# PSU24V_for_FAN.net
KiCad netlist of a schematic drawn in Altium Designer
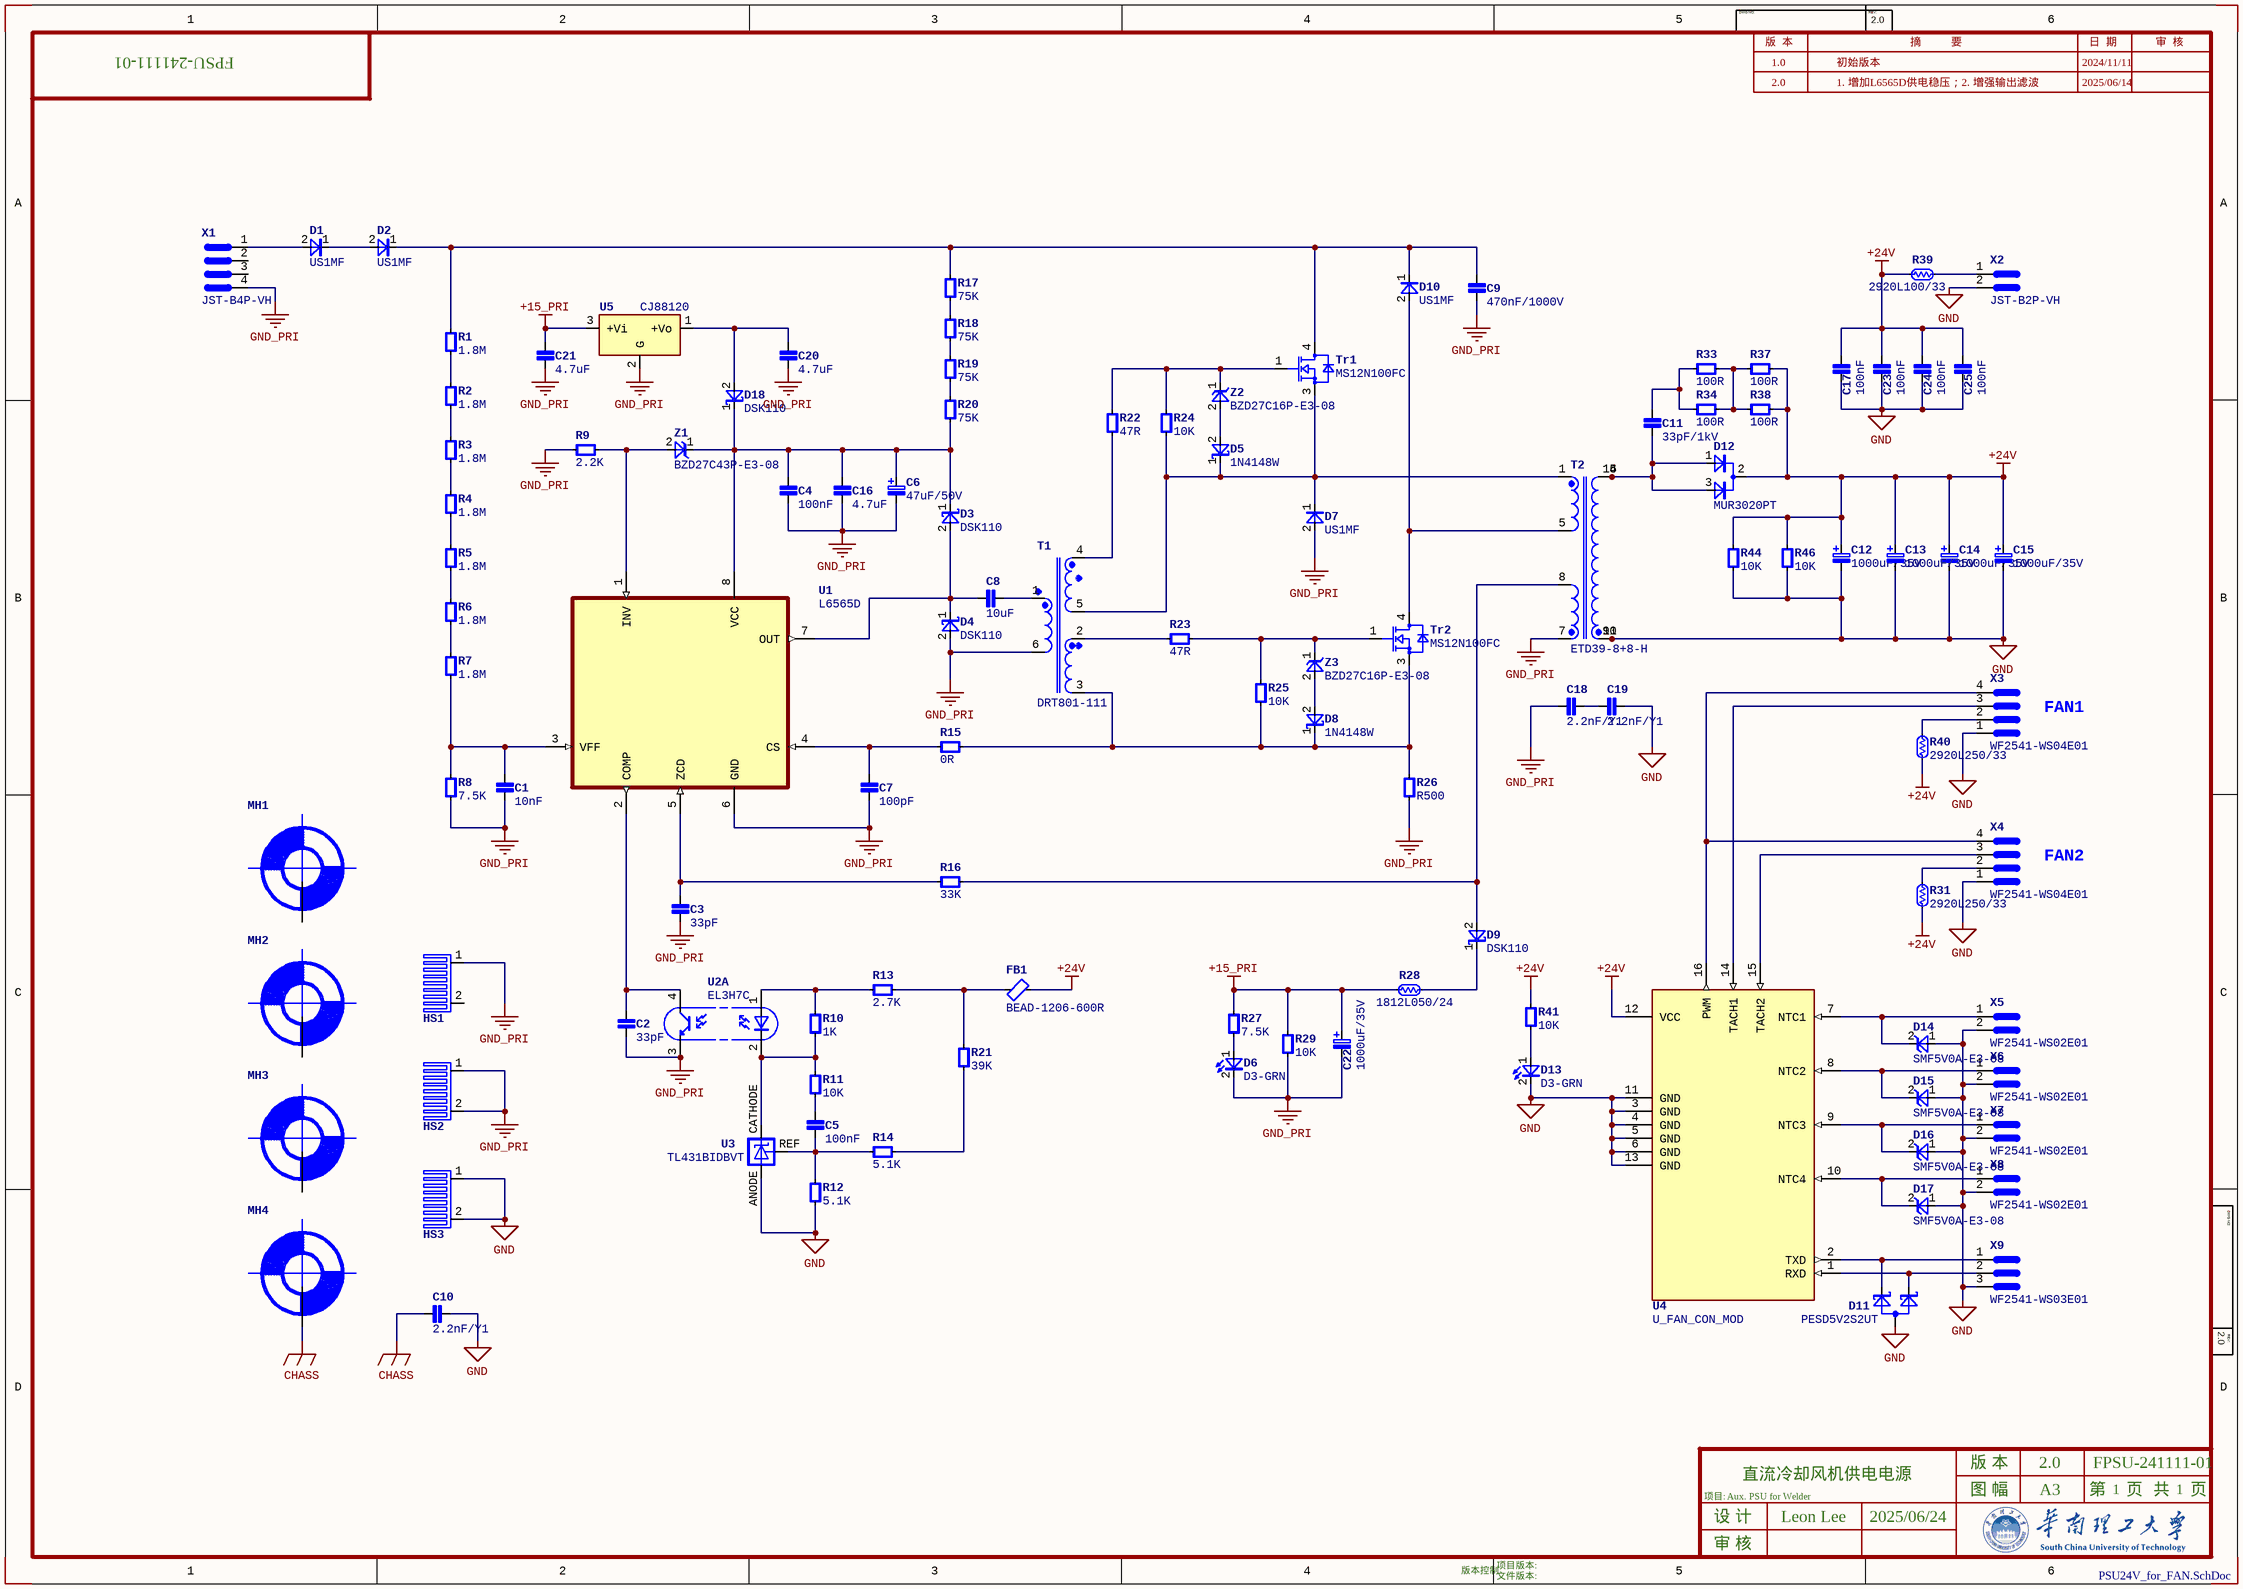
[diagram p0: PSU24V_for_FAN.SchDoc]

(export (version "E")
  (design (tool "Eeschema 10.0.6"))
  (components
    (comp (ref "C1")
      (value "10nF")
      (footprint "CAPC1206N")
      (libsource (lib "User_leo") (part "CAPACITOR(S)"))
    )
    (comp (ref "C2")
      (value "33pF")
      (footprint "CAPC1206N")
      (libsource (lib "User_leo") (part "CAPACITOR(S)"))
    )
    (comp (ref "C3")
      (value "33pF")
      (footprint "CAPC1206N")
      (libsource (lib "User_leo") (part "CAPACITOR(S)"))
    )
    (comp (ref "C4")
      (value "100nF")
      (footprint "CAPC1206N")
      (libsource (lib "User_leo") (part "CAPACITOR(S)"))
    )
    (comp (ref "C5") (value "100nF") (footprint "CAPC1206N") (libsource (lib "*") (part "CAPACITOR(S)")))
    (comp (ref "C6")
      (value "47uF/50V")
      (footprint "RB2.5M/D6.3")
      (libsource (lib "User_leo") (part "CAPACITOR POL(S)"))
    )
    (comp (ref "C7")
      (value "100pF")
      (footprint "CAPC1206N")
      (libsource (lib "User_leo") (part "CAPACITOR(S)"))
    )
    (comp (ref "C8")
      (value "10uF")
      (footprint "CAPC1206N")
      (libsource (lib "User_leo") (part "CAPACITOR(S)"))
    )
    (comp (ref "C9")
      (value "470nF/1000V")
      (footprint "PCM27.5-W17")
      (libsource (lib "User_leo") (part "CAPACITOR(S)"))
    )
    (comp (ref "C10")
      (value "2.2nF/Y1")
      (footprint "CAPRD10-10x5")
      (libsource (lib "User_leo") (part "CAPACITOR(S)"))
    )
    (comp (ref "C11")
      (value "33pF/1kV")
      (footprint "CAPC1206N")
      (libsource (lib "User_leo") (part "CAPACITOR(S)"))
    )
    (comp (ref "C12")
      (value "1000uF/35V")
      (footprint "RB5M/D10")
      (libsource (lib "User_leo") (part "CAPACITOR POL(S)"))
    )
    (comp (ref "C13")
      (value "1000uF/35V")
      (footprint "RB5M/D10")
      (libsource (lib "User_leo") (part "CAPACITOR POL(S)"))
    )
    (comp (ref "C14")
      (value "1000uF/35V")
      (footprint "RB5M/D10")
      (libsource (lib "User_leo") (part "CAPACITOR POL(S)"))
    )
    (comp (ref "C15")
      (value "1000uF/35V")
      (footprint "RB5M/D10")
      (libsource (lib "User_leo") (part "CAPACITOR POL(S)"))
    )
    (comp (ref "C16")
      (value "4.7uF")
      (footprint "CAPC1206N")
      (libsource (lib "User_leo") (part "CAPACITOR(S)"))
    )
    (comp (ref "C17")
      (value "100nF")
      (footprint "CAPC1206N")
      (libsource (lib "User_leo") (part "CAPACITOR(S)"))
    )
    (comp (ref "C18")
      (value "2.2nF/Y1")
      (footprint "CAPRD10-10x5")
      (libsource (lib "User_leo") (part "CAPACITOR(S)"))
    )
    (comp (ref "C19")
      (value "2.2nF/Y1")
      (footprint "CAPRD10-10x5")
      (libsource (lib "User_leo") (part "CAPACITOR(S)"))
    )
    (comp (ref "C20")
      (value "4.7uF")
      (footprint "CAPC1206N")
      (libsource (lib "User_leo") (part "CAPACITOR(S)"))
    )
    (comp (ref "C21")
      (value "4.7uF")
      (footprint "CAPC1206N")
      (libsource (lib "User_leo") (part "CAPACITOR(S)"))
    )
    (comp (ref "C22")
      (value "1000uF/35V")
      (footprint "RB5M/D10")
      (libsource (lib "User_leo") (part "CAPACITOR POL(S)"))
    )
    (comp (ref "C23")
      (value "100nF")
      (footprint "CAPC1206N")
      (libsource (lib "User_leo") (part "CAPACITOR(S)"))
    )
    (comp (ref "C24")
      (value "100nF")
      (footprint "CAPC1206N")
      (libsource (lib "User_leo") (part "CAPACITOR(S)"))
    )
    (comp (ref "C25")
      (value "100nF")
      (footprint "CAPC1206N")
      (libsource (lib "User_leo") (part "CAPACITOR(S)"))
    )
    (comp (ref "D1")
      (value "US1MF")
      (footprint "SMAF")
      (description "二极管")
      (libsource (lib "User_leo") (part "DIODE(S)"))
    )
    (comp (ref "D2")
      (value "US1MF")
      (footprint "SMAF")
      (description "二极管")
      (libsource (lib "User_leo") (part "DIODE(S)"))
    )
    (comp (ref "D3")
      (value "DSK110")
      (footprint "SMF-N-1K2A")
      (description "肖特基二极管")
      (libsource (lib "User_leo") (part "DIODE SCHOTTKY(S)"))
    )
    (comp (ref "D4")
      (value "DSK110")
      (footprint "SMF-N-1K2A")
      (description "肖特基二极管")
      (libsource (lib "User_leo") (part "DIODE SCHOTTKY(S)"))
    )
    (comp (ref "D5")
      (value "1N4148W")
      (footprint "SOD-123 - 1K2A")
      (description "肖特基二极管")
      (libsource (lib "User_leo") (part "DIODE SCHOTTKY(S)"))
    )
    (comp (ref "D6")
      (value "D3-GRN")
      (footprint "LED-D3")
      (description "发光二极管")
      (libsource (lib "User_leo") (part "LED(S)"))
    )
    (comp (ref "D7")
      (value "US1MF")
      (footprint "SMAF")
      (description "二极管")
      (libsource (lib "User_leo") (part "DIODE(S)"))
    )
    (comp (ref "D8")
      (value "1N4148W")
      (footprint "SOD-123 - 1K2A")
      (description "肖特基二极管")
      (libsource (lib "User_leo") (part "DIODE SCHOTTKY(S)"))
    )
    (comp (ref "D9")
      (value "DSK110")
      (footprint "SMF-N-1K2A")
      (description "肖特基二极管")
      (libsource (lib "User_leo") (part "DIODE SCHOTTKY(S)"))
    )
    (comp (ref "D10")
      (value "US1MF")
      (footprint "SMAF")
      (description "二极管")
      (libsource (lib "User_leo") (part "DIODE(S)"))
    )
    (comp (ref "D11")
      (value "PESD5V2S2UT")
      (footprint "SMD USER:SOT-23_N")
      (description "Schottky barrier (double) diodes")
      (libsource (lib "User_leo") (part "DIODE BAS40-06"))
    )
    (comp (ref "D12")
      (value "MUR3020PT")
      (footprint "PSU24_for_FAN:TO-247-3_Vertical")
      (description "快恢复二极管")
      (libsource (lib "User_leo") (part "DIODE MUR1620CT"))
    )
    (comp (ref "D13")
      (value "D3-GRN")
      (footprint "LED-D3")
      (description "发光二极管")
      (libsource (lib "User_leo") (part "LED(S)"))
    )
    (comp (ref "D14")
      (value "SMF5V0A-E3-08")
      (footprint "SMF-N")
      (description "齐纳二极管")
      (libsource (lib "User_leo") (part "DIODE ZENER(S)"))
    )
    (comp (ref "D15")
      (value "SMF5V0A-E3-08")
      (footprint "SMF-N")
      (description "齐纳二极管")
      (libsource (lib "User_leo") (part "DIODE ZENER(S)"))
    )
    (comp (ref "D16")
      (value "SMF5V0A-E3-08")
      (footprint "SMF-N")
      (description "齐纳二极管")
      (libsource (lib "User_leo") (part "DIODE ZENER(S)"))
    )
    (comp (ref "D17")
      (value "SMF5V0A-E3-08")
      (footprint "SMF-N")
      (description "齐纳二极管")
      (libsource (lib "User_leo") (part "DIODE ZENER(S)"))
    )
    (comp (ref "D18")
      (value "DSK110")
      (footprint "SMF-N-1K2A")
      (description "肖特基二极管")
      (libsource (lib "User_leo") (part "DIODE SCHOTTKY(S)"))
    )
    (comp (ref "FB1")
      (value "BEAD-1206-600R")
      (footprint "RESC1206N")
      (description "磁珠电感")
      (libsource (lib "User_leo") (part "FerriteBead1"))
    )
    (comp (ref "HS1")
      (value "HS-TO247-42x25x40")
      (footprint "HEATSINK_TO220_Vertical_42x25x38")
      (description "散热器, 2脚")
      (libsource (lib "User_leo") (part "HEATSINK_2PINS"))
    )
    (comp (ref "HS2")
      (value "HS-TO247-42x25x40")
      (footprint "HEATSINK_TO220_Vertical_42x25x38")
      (description "散热器, 2脚")
      (libsource (lib "User_leo") (part "HEATSINK_2PINS"))
    )
    (comp (ref "HS3")
      (value "HS-TO247-42x25x40")
      (footprint "HEATSINK_TO220_Vertical_42x25x38")
      (description "散热器, 2脚")
      (libsource (lib "User_leo") (part "HEATSINK_2PINS"))
    )
    (comp (ref "MH1")
      (value "MH1")
      (footprint "MH-D32-4x4")
      (description "安装孔")
      (libsource (lib "User_leo") (part "MH1"))
    )
    (comp (ref "MH2")
      (value "MH1")
      (footprint "MH-D32-4x4")
      (description "安装孔")
      (libsource (lib "User_leo") (part "MH1"))
    )
    (comp (ref "MH3")
      (value "MH1")
      (footprint "MH-D32-4x4")
      (description "安装孔")
      (libsource (lib "User_leo") (part "MH1"))
    )
    (comp (ref "MH4")
      (value "MH1")
      (footprint "MH-D32-4x4-PE")
      (description "安装孔")
      (libsource (lib "User_leo") (part "MH1"))
    )
    (comp (ref "R1")
      (value "1.8M")
      (footprint "RESC1206N")
      (description "电阻")
      (libsource (lib "User_leo") (part "RESISTOR(S)"))
    )
    (comp (ref "R2")
      (value "1.8M")
      (footprint "RESC1206N")
      (description "电阻")
      (libsource (lib "User_leo") (part "RESISTOR(S)"))
    )
    (comp (ref "R3")
      (value "1.8M")
      (footprint "RESC1206N")
      (description "电阻")
      (libsource (lib "User_leo") (part "RESISTOR(S)"))
    )
    (comp (ref "R4")
      (value "1.8M")
      (footprint "RESC1206N")
      (description "电阻")
      (libsource (lib "User_leo") (part "RESISTOR(S)"))
    )
    (comp (ref "R5")
      (value "1.8M")
      (footprint "RESC1206N")
      (description "电阻")
      (libsource (lib "User_leo") (part "RESISTOR(S)"))
    )
    (comp (ref "R6")
      (value "1.8M")
      (footprint "RESC1206N")
      (description "电阻")
      (libsource (lib "User_leo") (part "RESISTOR(S)"))
    )
    (comp (ref "R7")
      (value "1.8M")
      (footprint "RESC1206N")
      (description "电阻")
      (libsource (lib "User_leo") (part "RESISTOR(S)"))
    )
    (comp (ref "R8")
      (value "7.5K")
      (footprint "RESC1206N")
      (description "电阻")
      (libsource (lib "User_leo") (part "RESISTOR(S)"))
    )
    (comp (ref "R9")
      (value "2.2K")
      (footprint "RESC1206N")
      (description "电阻")
      (libsource (lib "User_leo") (part "RESISTOR(S)"))
    )
    (comp (ref "R10") (value "1K") (footprint "RESC1206N") (libsource (lib "*") (part "RESISTOR(S)")))
    (comp (ref "R11") (value "10K") (footprint "RESC1206N") (libsource (lib "*") (part "RESISTOR(S)")))
    (comp (ref "R12") (value "5.1K") (footprint "RESC1206N") (libsource (lib "*") (part "RESISTOR(S)")))
    (comp (ref "R13") (value "2.7K") (footprint "RESC1206N") (libsource (lib "*") (part "RESISTOR(S)")))
    (comp (ref "R14") (value "5.1K") (footprint "RESC1206N") (libsource (lib "*") (part "RESISTOR(S)")))
    (comp (ref "R15")
      (value "0R")
      (footprint "RESC1206N")
      (description "电阻")
      (libsource (lib "User_leo") (part "RESISTOR(S)"))
    )
    (comp (ref "R16")
      (value "33K")
      (footprint "RESC1206N")
      (description "电阻")
      (libsource (lib "User_leo") (part "RESISTOR(S)"))
    )
    (comp (ref "R17")
      (value "75K")
      (footprint "RESC1206N")
      (description "电阻")
      (libsource (lib "User_leo") (part "RESISTOR(S)"))
    )
    (comp (ref "R18")
      (value "75K")
      (footprint "RESC1206N")
      (description "电阻")
      (libsource (lib "User_leo") (part "RESISTOR(S)"))
    )
    (comp (ref "R19")
      (value "75K")
      (footprint "RESC1206N")
      (description "电阻")
      (libsource (lib "User_leo") (part "RESISTOR(S)"))
    )
    (comp (ref "R20")
      (value "75K")
      (footprint "RESC1206N")
      (description "电阻")
      (libsource (lib "User_leo") (part "RESISTOR(S)"))
    )
    (comp (ref "R21") (value "39K") (footprint "RESC1206N") (libsource (lib "*") (part "RESISTOR(S)")))
    (comp (ref "R22")
      (value "47R")
      (footprint "RESC1206N")
      (description "电阻")
      (libsource (lib "User_leo") (part "RESISTOR(S)"))
    )
    (comp (ref "R23")
      (value "47R")
      (footprint "RESC1206N")
      (description "电阻")
      (libsource (lib "User_leo") (part "RESISTOR(S)"))
    )
    (comp (ref "R24")
      (value "10K")
      (footprint "RESC1206N")
      (description "电阻")
      (libsource (lib "User_leo") (part "RESISTOR(S)"))
    )
    (comp (ref "R25")
      (value "10K")
      (footprint "RESC1206N")
      (description "电阻")
      (libsource (lib "User_leo") (part "RESISTOR(S)"))
    )
    (comp (ref "R26")
      (value "R500")
      (footprint "RESC1225N")
      (description "电阻")
      (libsource (lib "User_leo") (part "RESISTOR(S)"))
    )
    (comp (ref "R27") (value "7.5K") (footprint "RESC1206N") (libsource (lib "*") (part "RESISTOR(S)")))
    (comp (ref "R28")
      (value "1812L050/24")
      (footprint "PTCC1812N")
      (description "None Liner Resistor")
      (libsource (lib "User_leo") (part "RESISTOR(S) NL"))
    )
    (comp (ref "R29") (value "10K") (footprint "RESC1206N") (libsource (lib "*") (part "RESISTOR(S)")))
    (comp (ref "R31")
      (value "2920L250/33")
      (footprint "PTC2920N")
      (description "None Liner Resistor")
      (libsource (lib "User_leo") (part "RESISTOR(S) NL"))
    )
    (comp (ref "R33")
      (value "100R")
      (footprint "RESC1206N")
      (description "电阻")
      (libsource (lib "User_leo") (part "RESISTOR(S)"))
    )
    (comp (ref "R34")
      (value "100R")
      (footprint "RESC1206N")
      (description "电阻")
      (libsource (lib "User_leo") (part "RESISTOR(S)"))
    )
    (comp (ref "R37")
      (value "100R")
      (footprint "RESC1206N")
      (description "电阻")
      (libsource (lib "User_leo") (part "RESISTOR(S)"))
    )
    (comp (ref "R38")
      (value "100R")
      (footprint "RESC1206N")
      (description "电阻")
      (libsource (lib "User_leo") (part "RESISTOR(S)"))
    )
    (comp (ref "R39")
      (value "2920L100/33")
      (footprint "PTC2920N")
      (description "None Liner Resistor")
      (libsource (lib "User_leo") (part "RESISTOR(S) NL"))
    )
    (comp (ref "R40")
      (value "2920L250/33")
      (footprint "PTC2920N")
      (description "None Liner Resistor")
      (libsource (lib "User_leo") (part "RESISTOR(S) NL"))
    )
    (comp (ref "R41") (value "10K") (footprint "RESC1206N") (libsource (lib "*") (part "RESISTOR(S)")))
    (comp (ref "R44")
      (value "10K")
      (footprint "RESC1206N")
      (description "电阻")
      (libsource (lib "User_leo") (part "RESISTOR(S)"))
    )
    (comp (ref "R46")
      (value "10K")
      (footprint "RESC1206N")
      (description "电阻")
      (libsource (lib "User_leo") (part "RESISTOR(S)"))
    )
    (comp (ref "T1")
      (value "DRT801-111")
      (footprint "TRANS-DRT801-1+1+1")
      (description "IGBT驱动变压器, DRT801/111, 12.5x16.6mm")
      (libsource (lib "User_leo") (part "Transformer DRT801-111"))
    )
    (comp (ref "T2")
      (value "ETD39-8+8-H")
      (footprint "ETD39-8+8pins")
      (description "反激变压器，初级2组，次级2组，通用焊接电源风扇供电，24V+24V")
      (libsource (lib "User_leo") (part "TRANSFORM-Flyback_PSU_for_FAN"))
    )
    (comp (ref "Tr1")
      (value "MS12N100FC")
      (footprint "PSU24_for_FAN:TO-247-3_Vertical")
      (description "MOSFET N-CH D-PAK/TO252")
      (fields (field (name "MANUFACTURER") "Fairchild") (field (name "PART NUMBER") "SUD40N08-16-E3"))
      (libsource (lib "User_leo") (part "MOSFET - N-CH"))
    )
    (comp (ref "Tr2")
      (value "MS12N100FC")
      (footprint "PSU24_for_FAN:TO-247-3_Vertical")
      (description "MOSFET N-CH D-PAK/TO252")
      (fields (field (name "MANUFACTURER") "Fairchild") (field (name "PART NUMBER") "SUD40N08-16-E3"))
      (libsource (lib "User_leo") (part "MOSFET - N-CH"))
    )
    (comp (ref "U1")
      (value "L6565D")
      (footprint "SOIC-8N")
      (description "ST, QUASI-RESONANT SMPS CONTROLLER")
      (libsource (lib "User_leo") (part "L6565D"))
    )
    (comp (ref "U2")
      (value "EL3H7C")
      (footprint "FP-EL3H7-G-MFG")
      (libsource (lib "User_leo") (part "Optical-Couple"))
    )
    (comp (ref "U3")
      (value "TL431BIDBVT")
      (footprint "SOT23-5_N")
      (description "可调基准电压集成")
      (libsource (lib "d_user1") (part "TL431CLP"))
    )
    (comp (ref "U4")
      (value "U_FAN_CON_MOD")
      (footprint "U_FAN_CON")
      (description "直流风扇转速控制模块")
      (libsource (lib "User_leo") (part "U_FAN_CON_MOD"))
    )
    (comp (ref "U5") (value "CJ88120") (footprint "FP-SOT89-MFG") (libsource (lib "User_leo") (part "78LXX")))
    (comp (ref "X1")
      (value "JST-B4P-VH")
      (footprint "B4P-VH")
      (description "线路板接插件")
      (libsource (lib "User_leo") (part "4PIN-PCB-Connector"))
    )
    (comp (ref "X2")
      (value "JST-B2P-VH")
      (footprint "B2P-VH")
      (description "线路板接插件")
      (libsource (lib "User_leo") (part "2PIN-PCB-Connector"))
    )
    (comp (ref "X3")
      (value "WF2541-WS04E01")
      (footprint "PSU24_for_FAN:WF2541-WSXX01-4PIN")
      (description "线路板接插件")
      (libsource (lib "User_leo") (part "4PIN-PCB-Connector"))
    )
    (comp (ref "X4")
      (value "WF2541-WS04E01")
      (footprint "PSU24_for_FAN:WF2541-WSXX01-4PIN")
      (description "线路板接插件")
      (libsource (lib "User_leo") (part "4PIN-PCB-Connector"))
    )
    (comp (ref "X5")
      (value "WF2541-WS02E01")
      (footprint "PSU24_for_FAN:WF2541-WSXX01-2PIN")
      (description "线路板接插件")
      (libsource (lib "User_leo") (part "2PIN-PCB-Connector"))
    )
    (comp (ref "X6")
      (value "WF2541-WS02E01")
      (footprint "PSU24_for_FAN:WF2541-WSXX01-2PIN")
      (description "线路板接插件")
      (libsource (lib "User_leo") (part "2PIN-PCB-Connector"))
    )
    (comp (ref "X7")
      (value "WF2541-WS02E01")
      (footprint "PSU24_for_FAN:WF2541-WSXX01-2PIN")
      (description "线路板接插件")
      (libsource (lib "User_leo") (part "2PIN-PCB-Connector"))
    )
    (comp (ref "X8")
      (value "WF2541-WS02E01")
      (footprint "PSU24_for_FAN:WF2541-WSXX01-2PIN")
      (description "线路板接插件")
      (libsource (lib "User_leo") (part "2PIN-PCB-Connector"))
    )
    (comp (ref "X9")
      (value "WF2541-WS03E01")
      (footprint "WF2541-WSXX01-3PIN")
      (description "线路板接插件")
      (libsource (lib "User_leo") (part "3PIN-PCB-Connector"))
    )
    (comp (ref "Z1")
      (value "BZD27C43P-E3-08")
      (footprint "SOD-123 - 1K2A")
      (description "齐纳二极管")
      (libsource (lib "") (part "DIODE ZENER(S)_1"))
    )
    (comp (ref "Z2")
      (value "BZD27C16P-E3-08")
      (footprint "SOD-123 - 1K2A")
      (description "齐纳二极管")
      (libsource (lib "") (part "DIODE ZENER(S)_1"))
    )
    (comp (ref "Z3")
      (value "BZD27C16P-E3-08")
      (footprint "SOD-123 - 1K2A")
      (description "齐纳二极管")
      (libsource (lib "") (part "DIODE ZENER(S)_1"))
    )
  )
  (nets
    (net (code "1") (name "+15_PRI") (class "Default")
      (node (ref "C21") (pin "1") (pinfunction "1_1") (pintype "passive"))
      (node (ref "C22") (pin "1") (pinfunction "1_1") (pintype "passive"))
      (node (ref "R27") (pin "2") (pinfunction "2_2") (pintype "passive"))
      (node (ref "R28") (pin "1") (pinfunction "1_1") (pintype "passive"))
      (node (ref "R29") (pin "2") (pinfunction "2_2") (pintype "passive"))
      (node (ref "U5") (pin "3") (pinfunction "+Vi_3") (pintype "passive"))
    )
    (net (code "2") (name "+24V") (class "Default")
      (node (ref "C12") (pin "1") (pinfunction "1_1") (pintype "passive"))
      (node (ref "C13") (pin "1") (pinfunction "1_1") (pintype "passive"))
      (node (ref "C14") (pin "1") (pinfunction "1_1") (pintype "passive"))
      (node (ref "C15") (pin "1") (pinfunction "1_1") (pintype "passive"))
      (node (ref "C17") (pin "1") (pinfunction "1_1") (pintype "passive"))
      (node (ref "C23") (pin "1") (pinfunction "1_1") (pintype "passive"))
      (node (ref "C24") (pin "1") (pinfunction "1_1") (pintype "passive"))
      (node (ref "C25") (pin "1") (pinfunction "1_1") (pintype "passive"))
      (node (ref "D12") (pin "2") (pinfunction "K_2") (pintype "passive"))
      (node (ref "FB1") (pin "2") (pinfunction "2_2") (pintype "passive"))
      (node (ref "R31") (pin "1") (pinfunction "1_1") (pintype "passive"))
      (node (ref "R37") (pin "1") (pinfunction "1_1") (pintype "passive"))
      (node (ref "R38") (pin "1") (pinfunction "1_1") (pintype "passive"))
      (node (ref "R39") (pin "1") (pinfunction "1_1") (pintype "passive"))
      (node (ref "R40") (pin "1") (pinfunction "1_1") (pintype "passive"))
      (node (ref "R41") (pin "2") (pinfunction "2_2") (pintype "passive"))
      (node (ref "R44") (pin "1") (pinfunction "1_1") (pintype "passive"))
      (node (ref "R46") (pin "1") (pinfunction "1_1") (pintype "passive"))
      (node (ref "U4") (pin "12") (pinfunction "VCC_12") (pintype "power_in"))
    )
    (net (code "3") (name "CHASS") (class "Default")
      (node (ref "C10") (pin "2") (pinfunction "2_2") (pintype "passive"))
      (node (ref "MH4") (pin "0") (pinfunction "0_0") (pintype "passive"))
    )
    (net (code "4") (name "GND") (class "Default")
      (node (ref "C10") (pin "1") (pinfunction "1_1") (pintype "passive"))
      (node (ref "C12") (pin "2") (pinfunction "2_2") (pintype "passive"))
      (node (ref "C13") (pin "2") (pinfunction "2_2") (pintype "passive"))
      (node (ref "C14") (pin "2") (pinfunction "2_2") (pintype "passive"))
      (node (ref "C15") (pin "2") (pinfunction "2_2") (pintype "passive"))
      (node (ref "C17") (pin "2") (pinfunction "2_2") (pintype "passive"))
      (node (ref "C19") (pin "1") (pinfunction "1_1") (pintype "passive"))
      (node (ref "C23") (pin "2") (pinfunction "2_2") (pintype "passive"))
      (node (ref "C24") (pin "2") (pinfunction "2_2") (pintype "passive"))
      (node (ref "C25") (pin "2") (pinfunction "2_2") (pintype "passive"))
      (node (ref "D11") (pin "3") (pinfunction "A_3") (pintype "passive"))
      (node (ref "D13") (pin "2") (pinfunction "K_2") (pintype "passive"))
      (node (ref "D14") (pin "1") (pinfunction "A_1") (pintype "passive"))
      (node (ref "D15") (pin "1") (pinfunction "A_1") (pintype "passive"))
      (node (ref "D16") (pin "1") (pinfunction "A_1") (pintype "passive"))
      (node (ref "D17") (pin "1") (pinfunction "A_1") (pintype "passive"))
      (node (ref "HS3") (pin "1") (pinfunction "1_1") (pintype "passive"))
      (node (ref "HS3") (pin "2") (pinfunction "2_2") (pintype "passive"))
      (node (ref "R12") (pin "1") (pinfunction "1_1") (pintype "passive"))
      (node (ref "R44") (pin "2") (pinfunction "2_2") (pintype "passive"))
      (node (ref "R46") (pin "2") (pinfunction "2_2") (pintype "passive"))
      (node (ref "T2") (pin "10") (pintype "passive"))
      (node (ref "T2") (pin "11") (pintype "passive"))
      (node (ref "T2") (pin "9") (pintype "passive"))
      (node (ref "U3") (pin "ANODE") (pinfunction "ANODE_ANODE") (pintype "passive"))
      (node (ref "U4") (pin "11") (pinfunction "GND_11") (pintype "power_in"))
      (node (ref "U4") (pin "13") (pinfunction "GND_13") (pintype "power_in"))
      (node (ref "U4") (pin "3") (pinfunction "GND_3") (pintype "power_in"))
      (node (ref "U4") (pin "4") (pinfunction "GND_4") (pintype "power_in"))
      (node (ref "U4") (pin "5") (pinfunction "GND_5") (pintype "power_in"))
      (node (ref "U4") (pin "6") (pinfunction "GND_6") (pintype "power_in"))
      (node (ref "X2") (pin "2") (pinfunction "2_2") (pintype "passive"))
      (node (ref "X3") (pin "1") (pinfunction "1_1") (pintype "passive"))
      (node (ref "X4") (pin "1") (pinfunction "1_1") (pintype "passive"))
      (node (ref "X5") (pin "2") (pinfunction "2_2") (pintype "passive"))
      (node (ref "X6") (pin "2") (pinfunction "2_2") (pintype "passive"))
      (node (ref "X7") (pin "2") (pinfunction "2_2") (pintype "passive"))
      (node (ref "X8") (pin "2") (pinfunction "2_2") (pintype "passive"))
      (node (ref "X9") (pin "3") (pinfunction "3_3") (pintype "passive"))
    )
    (net (code "5") (name "GND_PRI") (class "Default")
      (node (ref "C1") (pin "2") (pinfunction "2_2") (pintype "passive"))
      (node (ref "C16") (pin "2") (pinfunction "2_2") (pintype "passive"))
      (node (ref "C18") (pin "2") (pinfunction "2_2") (pintype "passive"))
      (node (ref "C2") (pin "2") (pinfunction "2_2") (pintype "passive"))
      (node (ref "C20") (pin "2") (pinfunction "2_2") (pintype "passive"))
      (node (ref "C21") (pin "2") (pinfunction "2_2") (pintype "passive"))
      (node (ref "C22") (pin "2") (pinfunction "2_2") (pintype "passive"))
      (node (ref "C3") (pin "2") (pinfunction "2_2") (pintype "passive"))
      (node (ref "C4") (pin "2") (pinfunction "2_2") (pintype "passive"))
      (node (ref "C6") (pin "2") (pinfunction "2_2") (pintype "passive"))
      (node (ref "C7") (pin "2") (pinfunction "2_2") (pintype "passive"))
      (node (ref "C9") (pin "2") (pinfunction "2_2") (pintype "passive"))
      (node (ref "D4") (pin "2") (pinfunction "A_2") (pintype "passive"))
      (node (ref "D6") (pin "2") (pinfunction "K_2") (pintype "passive"))
      (node (ref "D7") (pin "2") (pinfunction "A_2") (pintype "passive"))
      (node (ref "HS1") (pin "1") (pinfunction "1_1") (pintype "passive"))
      (node (ref "HS2") (pin "1") (pinfunction "1_1") (pintype "passive"))
      (node (ref "HS2") (pin "2") (pinfunction "2_2") (pintype "passive"))
      (node (ref "R26") (pin "2") (pinfunction "2_2") (pintype "passive"))
      (node (ref "R29") (pin "1") (pinfunction "1_1") (pintype "passive"))
      (node (ref "R8") (pin "2") (pinfunction "2_2") (pintype "passive"))
      (node (ref "R9") (pin "2") (pinfunction "2_2") (pintype "passive"))
      (node (ref "T1") (pin "6") (pinfunction "6_6") (pintype "passive"))
      (node (ref "T2") (pin "7") (pintype "passive"))
      (node (ref "U1") (pin "6") (pinfunction "GND_6") (pintype "power_in"))
      (node (ref "U2") (pin "3") (pinfunction "E_3") (pintype "passive"))
      (node (ref "U5") (pin "2") (pinfunction "G_2") (pintype "passive"))
      (node (ref "X1") (pin "4") (pinfunction "4_4") (pintype "passive"))
    )
    (net (code "6") (name "Net-(C5-Pad1)") (class "Default")
      (node (ref "C5") (pin "1") (pinfunction "1_1") (pintype "passive"))
      (node (ref "R11") (pin "1") (pinfunction "1_1") (pintype "passive"))
    )
    (net (code "7") (name "Net-(C5-Pad2)") (class "Default")
      (node (ref "C5") (pin "2") (pinfunction "2_2") (pintype "passive"))
      (node (ref "R12") (pin "2") (pinfunction "2_2") (pintype "passive"))
      (node (ref "R14") (pin "1") (pinfunction "1_1") (pintype "passive"))
      (node (ref "U3") (pin "REF") (pinfunction "REF_REF") (pintype "passive"))
    )
    (net (code "8") (name "Net-(C8-Pad2)") (class "Default")
      (node (ref "C8") (pin "2") (pinfunction "2_2") (pintype "passive"))
      (node (ref "T1") (pin "1") (pinfunction "1_1") (pintype "passive"))
    )
    (net (code "9") (name "Net-(C11-Pad1)") (class "Default")
      (node (ref "C11") (pin "1") (pinfunction "1_1") (pintype "passive"))
      (node (ref "R33") (pin "2") (pinfunction "2_2") (pintype "passive"))
      (node (ref "R34") (pin "2") (pinfunction "2_2") (pintype "passive"))
    )
    (net (code "10") (name "Net-(C11-Pad2)") (class "Default")
      (node (ref "C11") (pin "2") (pinfunction "2_2") (pintype "passive"))
      (node (ref "D12") (pin "1") (pinfunction "A_1") (pintype "passive"))
      (node (ref "D12") (pin "3") (pinfunction "A_3") (pintype "passive"))
      (node (ref "T2") (pin "14") (pintype "passive"))
      (node (ref "T2") (pin "15") (pintype "passive"))
      (node (ref "T2") (pin "16") (pintype "passive"))
    )
    (net (code "11") (name "Net-(C18-Pad1)") (class "Default")
      (node (ref "C18") (pin "1") (pinfunction "1_1") (pintype "passive"))
      (node (ref "C19") (pin "2") (pinfunction "2_2") (pintype "passive"))
    )
    (net (code "12") (name "Net-(D1-A)") (class "Default")
      (node (ref "D1") (pin "2") (pinfunction "A_2") (pintype "passive"))
      (node (ref "X1") (pin "1") (pinfunction "1_1") (pintype "passive"))
    )
    (net (code "13") (name "Net-(D1-K)") (class "Default")
      (node (ref "D1") (pin "1") (pinfunction "K_1") (pintype "passive"))
      (node (ref "D2") (pin "2") (pinfunction "A_2") (pintype "passive"))
    )
    (net (code "14") (name "Net-(D3-A)") (class "Default")
      (node (ref "C8") (pin "1") (pinfunction "1_1") (pintype "passive"))
      (node (ref "D3") (pin "2") (pinfunction "A_2") (pintype "passive"))
      (node (ref "D4") (pin "1") (pinfunction "K_1") (pintype "passive"))
      (node (ref "U1") (pin "7") (pinfunction "OUT_7") (pintype "output"))
    )
    (net (code "15") (name "Net-(D5-A)") (class "Default")
      (node (ref "D5") (pin "2") (pinfunction "A_2") (pintype "passive"))
      (node (ref "Z2") (pin "2") (pinfunction "A_2") (pintype "passive"))
    )
    (net (code "16") (name "Net-(D5-K)") (class "Default")
      (node (ref "D5") (pin "1") (pinfunction "K_1") (pintype "passive"))
      (node (ref "D7") (pin "1") (pinfunction "K_1") (pintype "passive"))
      (node (ref "R24") (pin "1") (pinfunction "1_1") (pintype "passive"))
      (node (ref "T1") (pin "5") (pinfunction "5_5") (pintype "passive"))
      (node (ref "T2") (pin "1") (pintype "passive"))
      (node (ref "Tr1") (pin "3") (pinfunction "S_3") (pintype "passive"))
    )
    (net (code "17") (name "Net-(D6-A)") (class "Default")
      (node (ref "D6") (pin "1") (pinfunction "A_1") (pintype "passive"))
      (node (ref "R27") (pin "1") (pinfunction "1_1") (pintype "passive"))
    )
    (net (code "18") (name "Net-(D8-A)") (class "Default")
      (node (ref "D8") (pin "2") (pinfunction "A_2") (pintype "passive"))
      (node (ref "Z3") (pin "2") (pinfunction "A_2") (pintype "passive"))
    )
    (net (code "19") (name "Net-(D8-K)") (class "Default")
      (node (ref "D8") (pin "1") (pinfunction "K_1") (pintype "passive"))
      (node (ref "R15") (pin "2") (pinfunction "2_2") (pintype "passive"))
      (node (ref "R25") (pin "1") (pinfunction "1_1") (pintype "passive"))
      (node (ref "R26") (pin "1") (pinfunction "1_1") (pintype "passive"))
      (node (ref "T1") (pin "3") (pinfunction "3_3") (pintype "passive"))
      (node (ref "Tr2") (pin "3") (pinfunction "S_3") (pintype "passive"))
    )
    (net (code "20") (name "Net-(D9-A)") (class "Default")
      (node (ref "D9") (pin "2") (pinfunction "A_2") (pintype "passive"))
      (node (ref "R16") (pin "2") (pinfunction "2_2") (pintype "passive"))
      (node (ref "T2") (pin "8") (pintype "passive"))
    )
    (net (code "21") (name "Net-(D9-K)") (class "Default")
      (node (ref "D9") (pin "1") (pinfunction "K_1") (pintype "passive"))
      (node (ref "R28") (pin "2") (pinfunction "2_2") (pintype "passive"))
    )
    (net (code "22") (name "Net-(D10-A)") (class "Default")
      (node (ref "D10") (pin "2") (pinfunction "A_2") (pintype "passive"))
      (node (ref "T2") (pin "5") (pintype "passive"))
      (node (ref "Tr2") (pin "4") (pinfunction "D_4") (pintype "passive"))
    )
    (net (code "23") (name "Net-(D10-K)") (class "Default")
      (node (ref "C9") (pin "1") (pinfunction "1_1") (pintype "passive"))
      (node (ref "D10") (pin "1") (pinfunction "K_1") (pintype "passive"))
      (node (ref "D2") (pin "1") (pinfunction "K_1") (pintype "passive"))
      (node (ref "R1") (pin "1") (pinfunction "1_1") (pintype "passive"))
      (node (ref "R17") (pin "2") (pinfunction "2_2") (pintype "passive"))
      (node (ref "Tr1") (pin "4") (pinfunction "D_4") (pintype "passive"))
    )
    (net (code "24") (name "Net-(D11-K1)") (class "Default")
      (node (ref "D11") (pin "1") (pinfunction "K1_1") (pintype "passive"))
      (node (ref "U4") (pin "2") (pinfunction "TXD_2") (pintype "output"))
      (node (ref "X9") (pin "1") (pinfunction "1_1") (pintype "passive"))
    )
    (net (code "25") (name "Net-(D11-K2)") (class "Default")
      (node (ref "D11") (pin "2") (pinfunction "K2_2") (pintype "passive"))
      (node (ref "U4") (pin "1") (pinfunction "RXD_1") (pintype "input"))
      (node (ref "X9") (pin "2") (pinfunction "2_2") (pintype "passive"))
    )
    (net (code "26") (name "Net-(D13-A)") (class "Default")
      (node (ref "D13") (pin "1") (pinfunction "A_1") (pintype "passive"))
      (node (ref "R41") (pin "1") (pinfunction "1_1") (pintype "passive"))
    )
    (net (code "27") (name "Net-(D14-K)") (class "Default")
      (node (ref "D14") (pin "2") (pinfunction "K_2") (pintype "passive"))
      (node (ref "U4") (pin "7") (pinfunction "NTC1_7") (pintype "input"))
      (node (ref "X5") (pin "1") (pinfunction "1_1") (pintype "passive"))
    )
    (net (code "28") (name "Net-(D15-K)") (class "Default")
      (node (ref "D15") (pin "2") (pinfunction "K_2") (pintype "passive"))
      (node (ref "U4") (pin "8") (pinfunction "NTC2_8") (pintype "input"))
      (node (ref "X6") (pin "1") (pinfunction "1_1") (pintype "passive"))
    )
    (net (code "29") (name "Net-(D16-K)") (class "Default")
      (node (ref "D16") (pin "2") (pinfunction "K_2") (pintype "passive"))
      (node (ref "U4") (pin "9") (pinfunction "NTC3_9") (pintype "input"))
      (node (ref "X7") (pin "1") (pinfunction "1_1") (pintype "passive"))
    )
    (net (code "30") (name "Net-(D17-K)") (class "Default")
      (node (ref "D17") (pin "2") (pinfunction "K_2") (pintype "passive"))
      (node (ref "U4") (pin "10") (pinfunction "NTC4_10") (pintype "input"))
      (node (ref "X8") (pin "1") (pinfunction "1_1") (pintype "passive"))
    )
    (net (code "31") (name "Net-(D18-A)") (class "Default")
      (node (ref "C20") (pin "1") (pinfunction "1_1") (pintype "passive"))
      (node (ref "D18") (pin "2") (pinfunction "A_2") (pintype "passive"))
      (node (ref "U5") (pin "1") (pinfunction "+Vo_1") (pintype "passive"))
    )
    (net (code "32") (name "Net-(D18-K)") (class "Default")
      (node (ref "C16") (pin "1") (pinfunction "1_1") (pintype "passive"))
      (node (ref "C4") (pin "1") (pinfunction "1_1") (pintype "passive"))
      (node (ref "C6") (pin "1") (pinfunction "1_1") (pintype "passive"))
      (node (ref "D18") (pin "1") (pinfunction "K_1") (pintype "passive"))
      (node (ref "D3") (pin "1") (pinfunction "K_1") (pintype "passive"))
      (node (ref "R20") (pin "1") (pinfunction "1_1") (pintype "passive"))
      (node (ref "U1") (pin "8") (pinfunction "VCC_8") (pintype "power_in"))
      (node (ref "Z1") (pin "1") (pinfunction "K_1") (pintype "passive"))
    )
    (net (code "33") (name "Net-(FB1-Pad1)") (class "Default")
      (node (ref "FB1") (pin "1") (pinfunction "1_1") (pintype "passive"))
      (node (ref "R13") (pin "2") (pinfunction "2_2") (pintype "passive"))
      (node (ref "R21") (pin "2") (pinfunction "2_2") (pintype "passive"))
    )
    (net (code "34") (name "Net-(R1-Pad2)") (class "Default")
      (node (ref "R1") (pin "2") (pinfunction "2_2") (pintype "passive"))
      (node (ref "R2") (pin "1") (pinfunction "1_1") (pintype "passive"))
    )
    (net (code "35") (name "Net-(R2-Pad2)") (class "Default")
      (node (ref "R2") (pin "2") (pinfunction "2_2") (pintype "passive"))
      (node (ref "R3") (pin "1") (pinfunction "1_1") (pintype "passive"))
    )
    (net (code "36") (name "Net-(R3-Pad2)") (class "Default")
      (node (ref "R3") (pin "2") (pinfunction "2_2") (pintype "passive"))
      (node (ref "R4") (pin "1") (pinfunction "1_1") (pintype "passive"))
    )
    (net (code "37") (name "Net-(R4-Pad2)") (class "Default")
      (node (ref "R4") (pin "2") (pinfunction "2_2") (pintype "passive"))
      (node (ref "R5") (pin "1") (pinfunction "1_1") (pintype "passive"))
    )
    (net (code "38") (name "Net-(R5-Pad2)") (class "Default")
      (node (ref "R5") (pin "2") (pinfunction "2_2") (pintype "passive"))
      (node (ref "R6") (pin "1") (pinfunction "1_1") (pintype "passive"))
    )
    (net (code "39") (name "Net-(R6-Pad2)") (class "Default")
      (node (ref "R6") (pin "2") (pinfunction "2_2") (pintype "passive"))
      (node (ref "R7") (pin "1") (pinfunction "1_1") (pintype "passive"))
    )
    (net (code "40") (name "Net-(R14-Pad2)") (class "Default")
      (node (ref "R14") (pin "2") (pinfunction "2_2") (pintype "passive"))
      (node (ref "R21") (pin "1") (pinfunction "1_1") (pintype "passive"))
    )
    (net (code "41") (name "Net-(R17-Pad1)") (class "Default")
      (node (ref "R17") (pin "1") (pinfunction "1_1") (pintype "passive"))
      (node (ref "R18") (pin "2") (pinfunction "2_2") (pintype "passive"))
    )
    (net (code "42") (name "Net-(R18-Pad1)") (class "Default")
      (node (ref "R18") (pin "1") (pinfunction "1_1") (pintype "passive"))
      (node (ref "R19") (pin "2") (pinfunction "2_2") (pintype "passive"))
    )
    (net (code "43") (name "Net-(R19-Pad1)") (class "Default")
      (node (ref "R19") (pin "1") (pinfunction "1_1") (pintype "passive"))
      (node (ref "R20") (pin "2") (pinfunction "2_2") (pintype "passive"))
    )
    (net (code "44") (name "Net-(R22-Pad1)") (class "Default")
      (node (ref "R22") (pin "1") (pinfunction "1_1") (pintype "passive"))
      (node (ref "T1") (pin "4") (pinfunction "4_4") (pintype "passive"))
    )
    (net (code "45") (name "Net-(R23-Pad2)") (class "Default")
      (node (ref "R23") (pin "2") (pinfunction "2_2") (pintype "passive"))
      (node (ref "T1") (pin "2") (pinfunction "2_2") (pintype "passive"))
    )
    (net (code "46") (name "Net-(R31-Pad2)") (class "Default")
      (node (ref "R31") (pin "2") (pinfunction "2_2") (pintype "passive"))
      (node (ref "X4") (pin "2") (pinfunction "2_2") (pintype "passive"))
    )
    (net (code "47") (name "Net-(R33-Pad1)") (class "Default")
      (node (ref "R33") (pin "1") (pinfunction "1_1") (pintype "passive"))
      (node (ref "R34") (pin "1") (pinfunction "1_1") (pintype "passive"))
      (node (ref "R37") (pin "2") (pinfunction "2_2") (pintype "passive"))
      (node (ref "R38") (pin "2") (pinfunction "2_2") (pintype "passive"))
    )
    (net (code "48") (name "Net-(R39-Pad2)") (class "Default")
      (node (ref "R39") (pin "2") (pinfunction "2_2") (pintype "passive"))
      (node (ref "X2") (pin "1") (pinfunction "1_1") (pintype "passive"))
    )
    (net (code "49") (name "Net-(R40-Pad2)") (class "Default")
      (node (ref "R40") (pin "2") (pinfunction "2_2") (pintype "passive"))
      (node (ref "X3") (pin "2") (pinfunction "2_2") (pintype "passive"))
    )
    (net (code "50") (name "Net-(Tr1-G)") (class "Default")
      (node (ref "R22") (pin "2") (pinfunction "2_2") (pintype "passive"))
      (node (ref "R24") (pin "2") (pinfunction "2_2") (pintype "passive"))
      (node (ref "Tr1") (pin "1") (pinfunction "G_1") (pintype "passive"))
      (node (ref "Z2") (pin "1") (pinfunction "K_1") (pintype "passive"))
    )
    (net (code "51") (name "Net-(Tr2-G)") (class "Default")
      (node (ref "R23") (pin "1") (pinfunction "1_1") (pintype "passive"))
      (node (ref "R25") (pin "2") (pinfunction "2_2") (pintype "passive"))
      (node (ref "Tr2") (pin "1") (pinfunction "G_1") (pintype "passive"))
      (node (ref "Z3") (pin "1") (pinfunction "K_1") (pintype "passive"))
    )
    (net (code "52") (name "Net-(U1-COMP)") (class "Default")
      (node (ref "C2") (pin "1") (pinfunction "1_1") (pintype "passive"))
      (node (ref "U1") (pin "2") (pinfunction "COMP_2") (pintype "output"))
      (node (ref "U2") (pin "4") (pinfunction "C_4") (pintype "passive"))
    )
    (net (code "53") (name "Net-(U1-CS)") (class "Default")
      (node (ref "C7") (pin "1") (pinfunction "1_1") (pintype "passive"))
      (node (ref "R15") (pin "1") (pinfunction "1_1") (pintype "passive"))
      (node (ref "U1") (pin "4") (pinfunction "CS_4") (pintype "input"))
    )
    (net (code "54") (name "Net-(U1-INV)") (class "Default")
      (node (ref "R9") (pin "1") (pinfunction "1_1") (pintype "passive"))
      (node (ref "U1") (pin "1") (pinfunction "INV_1") (pintype "input"))
      (node (ref "Z1") (pin "2") (pinfunction "A_2") (pintype "passive"))
    )
    (net (code "55") (name "Net-(U1-VFF)") (class "Default")
      (node (ref "C1") (pin "1") (pinfunction "1_1") (pintype "passive"))
      (node (ref "R7") (pin "2") (pinfunction "2_2") (pintype "passive"))
      (node (ref "R8") (pin "1") (pinfunction "1_1") (pintype "passive"))
      (node (ref "U1") (pin "3") (pinfunction "VFF_3") (pintype "input"))
    )
    (net (code "56") (name "Net-(U1-ZCD)") (class "Default")
      (node (ref "C3") (pin "1") (pinfunction "1_1") (pintype "passive"))
      (node (ref "R16") (pin "1") (pinfunction "1_1") (pintype "passive"))
      (node (ref "U1") (pin "5") (pinfunction "ZCD_5") (pintype "input"))
    )
    (net (code "57") (name "Net-(U2A-A)") (class "Default")
      (node (ref "R10") (pin "2") (pinfunction "2_2") (pintype "passive"))
      (node (ref "R13") (pin "1") (pinfunction "1_1") (pintype "passive"))
      (node (ref "U2") (pin "1") (pinfunction "A_1") (pintype "passive"))
    )
    (net (code "58") (name "Net-(U2A-K)") (class "Default")
      (node (ref "R10") (pin "1") (pinfunction "1_1") (pintype "passive"))
      (node (ref "R11") (pin "2") (pinfunction "2_2") (pintype "passive"))
      (node (ref "U2") (pin "2") (pinfunction "K_2") (pintype "passive"))
      (node (ref "U3") (pin "CATHODE") (pinfunction "CATHODE_CATHODE") (pintype "passive"))
    )
    (net (code "59") (name "Net-(U4-PWM)") (class "Default")
      (node (ref "U4") (pin "16") (pinfunction "PWM_16") (pintype "output"))
      (node (ref "X3") (pin "4") (pinfunction "4_4") (pintype "passive"))
      (node (ref "X4") (pin "4") (pinfunction "4_4") (pintype "passive"))
    )
    (net (code "60") (name "Net-(U4-TACH1)") (class "Default")
      (node (ref "U4") (pin "14") (pinfunction "TACH1_14") (pintype "input"))
      (node (ref "X3") (pin "3") (pinfunction "3_3") (pintype "passive"))
    )
    (net (code "61") (name "Net-(U4-TACH2)") (class "Default")
      (node (ref "U4") (pin "15") (pinfunction "TACH2_15") (pintype "input"))
      (node (ref "X4") (pin "3") (pinfunction "3_3") (pintype "passive"))
    )
    (net (code "62") (name "unconnected-(HS1-Pad2)") (class "Default")
      (node (ref "HS1") (pin "2") (pinfunction "2_2") (pintype "passive"))
    )
    (net (code "63") (name "unconnected-(MH1-Pad0)") (class "Default")
      (node (ref "MH1") (pin "0") (pinfunction "0_0") (pintype "passive"))
    )
    (net (code "64") (name "unconnected-(MH2-Pad0)") (class "Default")
      (node (ref "MH2") (pin "0") (pinfunction "0_0") (pintype "passive"))
    )
    (net (code "65") (name "unconnected-(MH3-Pad0)") (class "Default")
      (node (ref "MH3") (pin "0") (pinfunction "0_0") (pintype "passive"))
    )
    (net (code "66") (name "unconnected-(X1-Pad2)") (class "Default")
      (node (ref "X1") (pin "2") (pinfunction "2_2") (pintype "passive"))
    )
    (net (code "67") (name "unconnected-(X1-Pad3)") (class "Default")
      (node (ref "X1") (pin "3") (pinfunction "3_3") (pintype "passive"))
    )
  )
)
